# Orange_Board.net
KiCad netlist of a schematic drawn in EAGLE
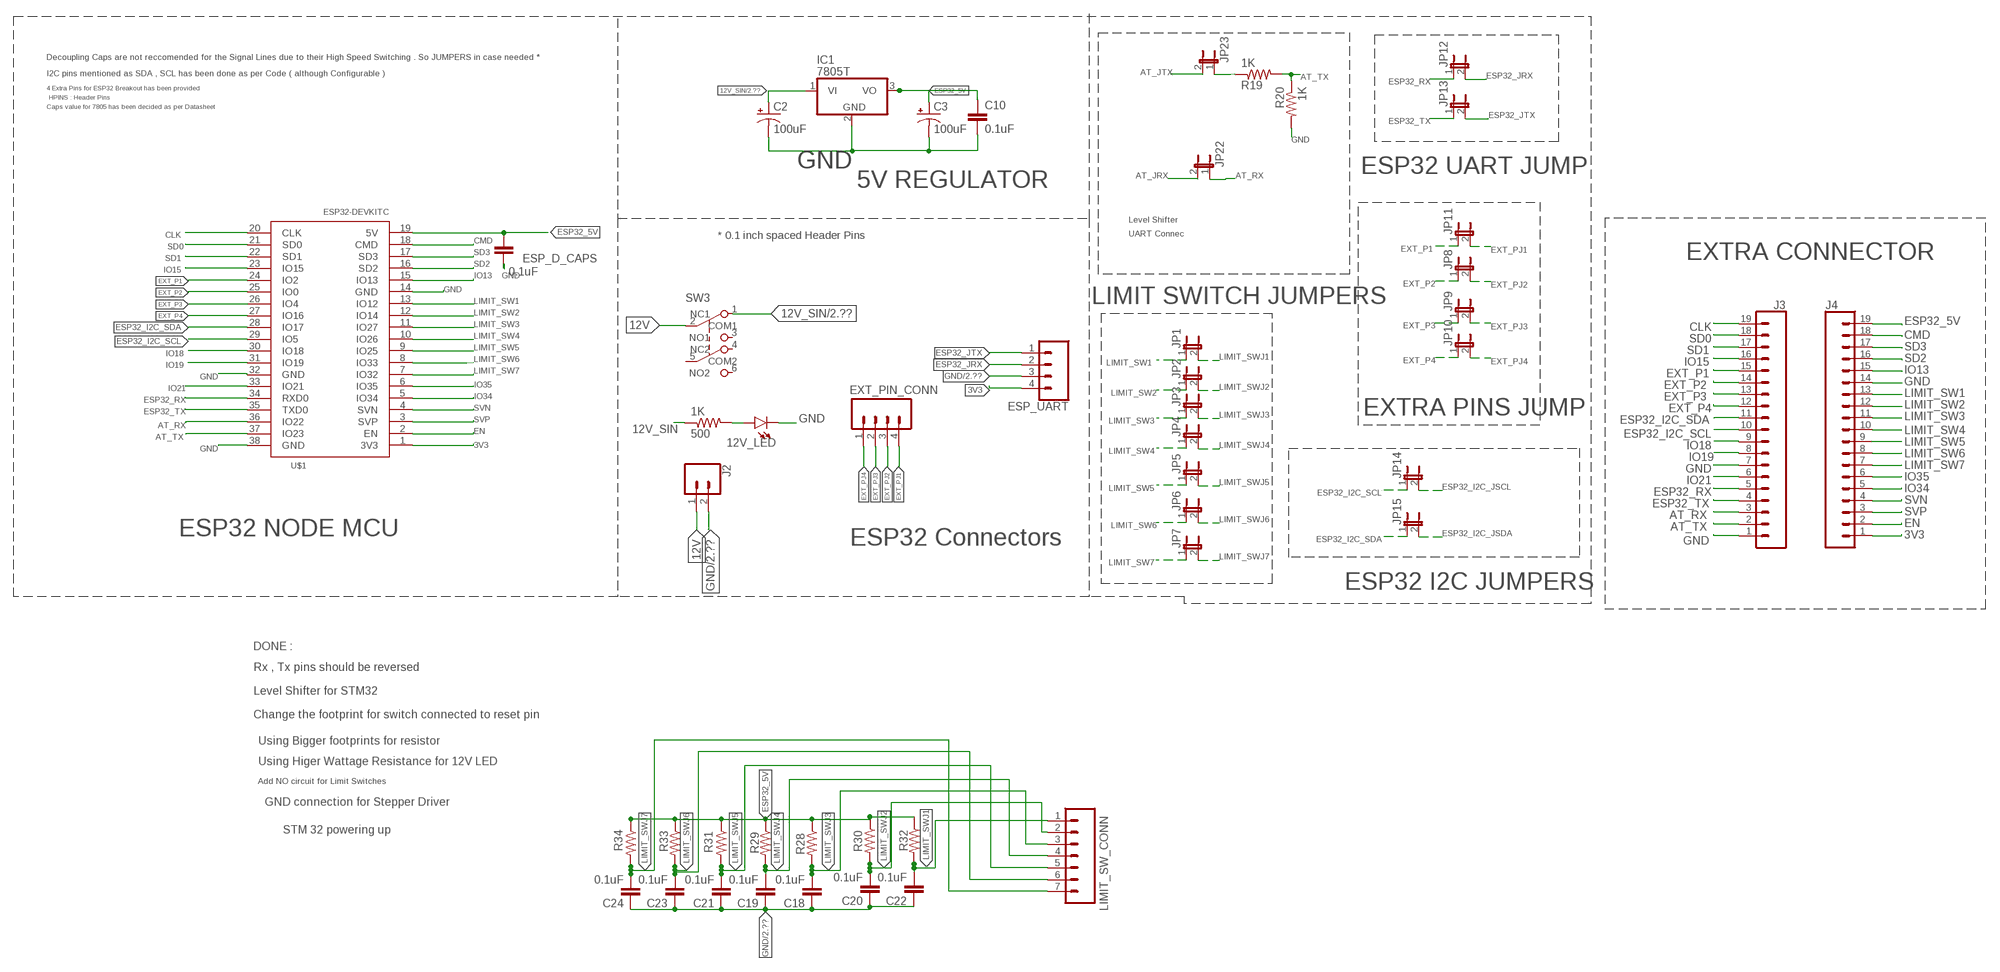
[diagram p0: schematic, sheet 1]
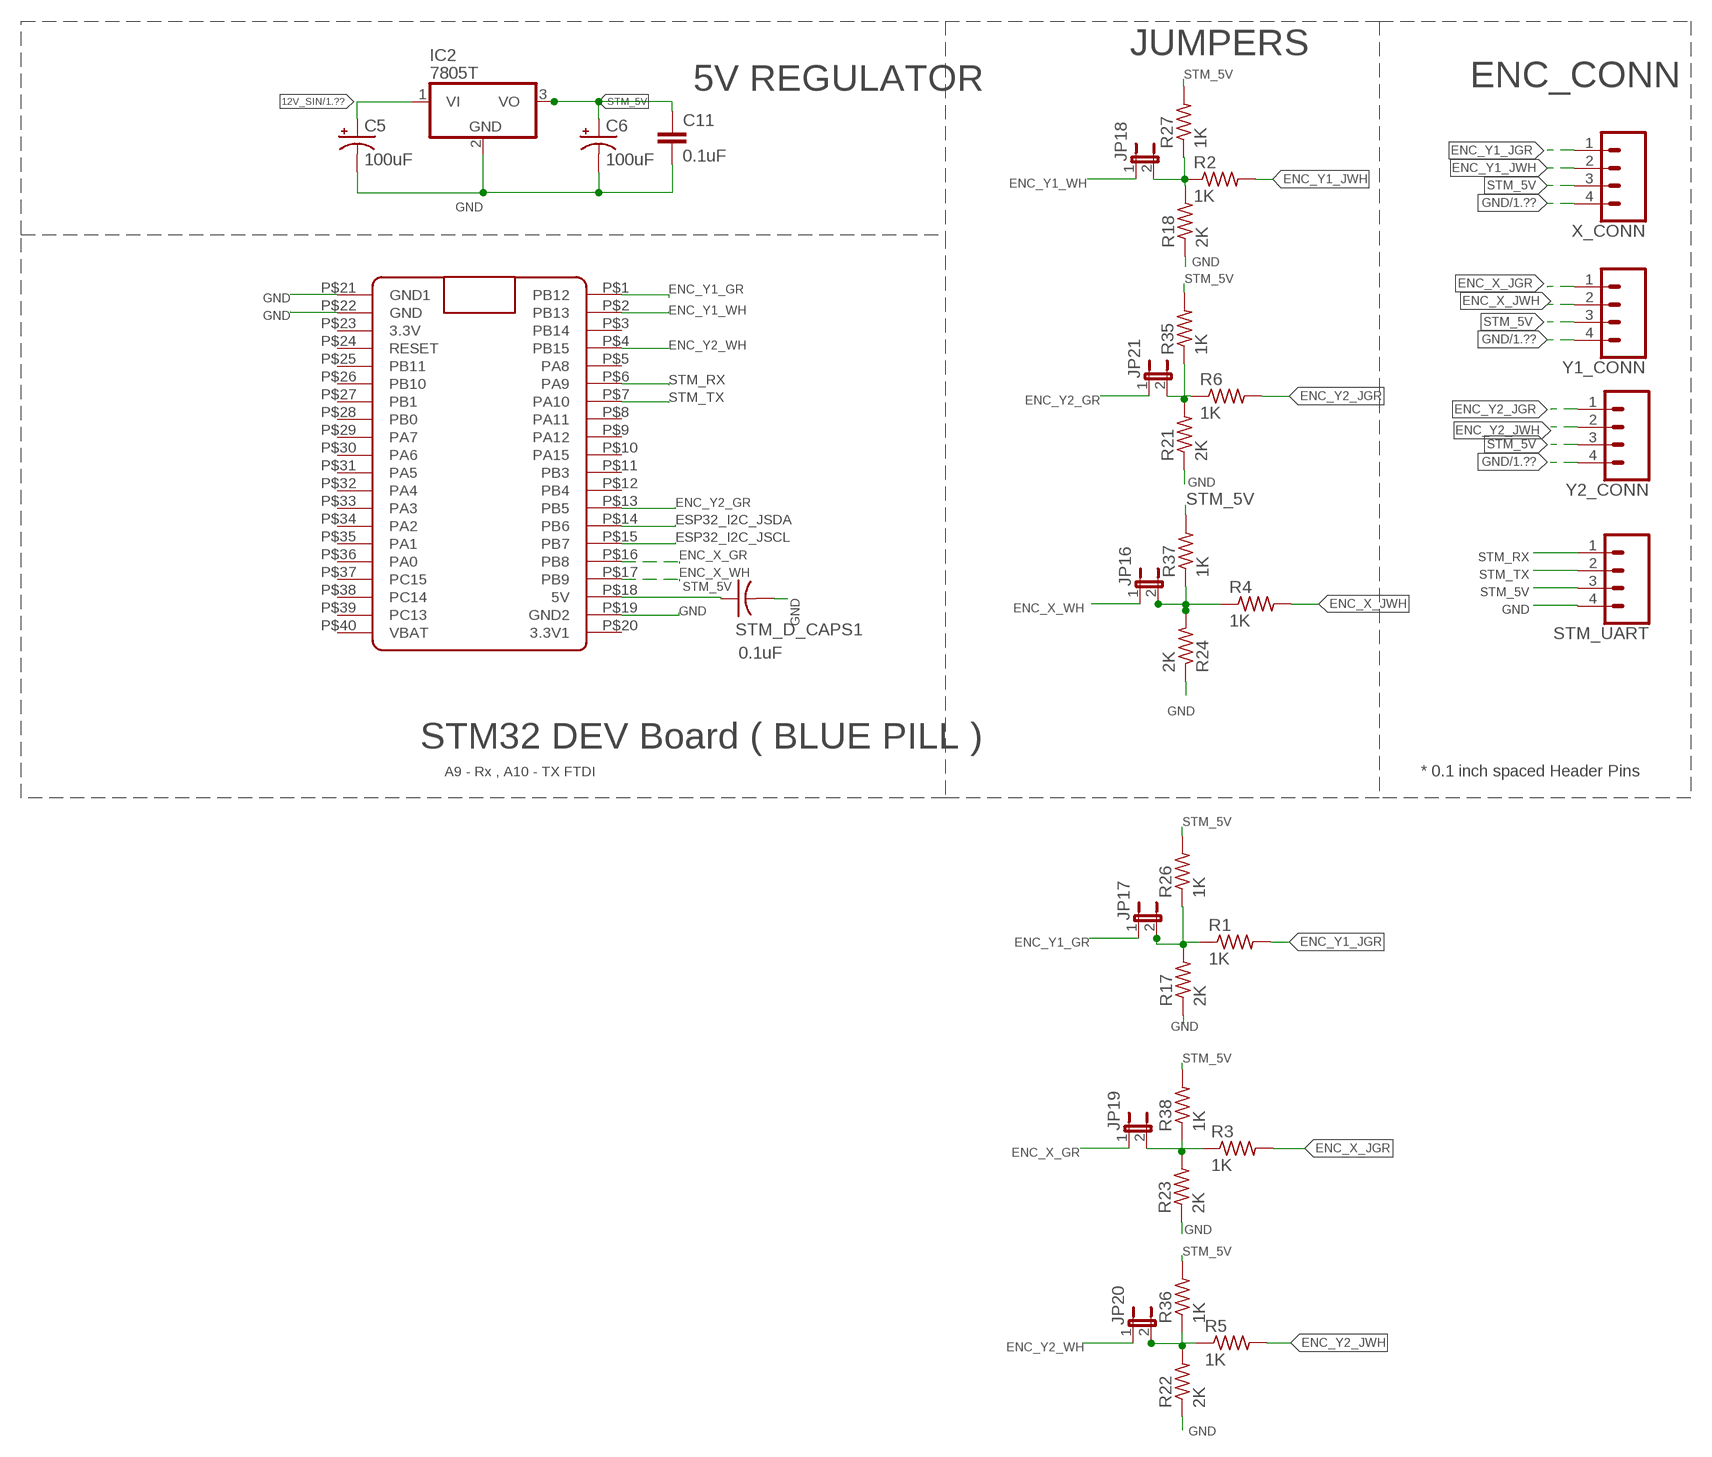
[diagram p1: schematic, sheet 2]
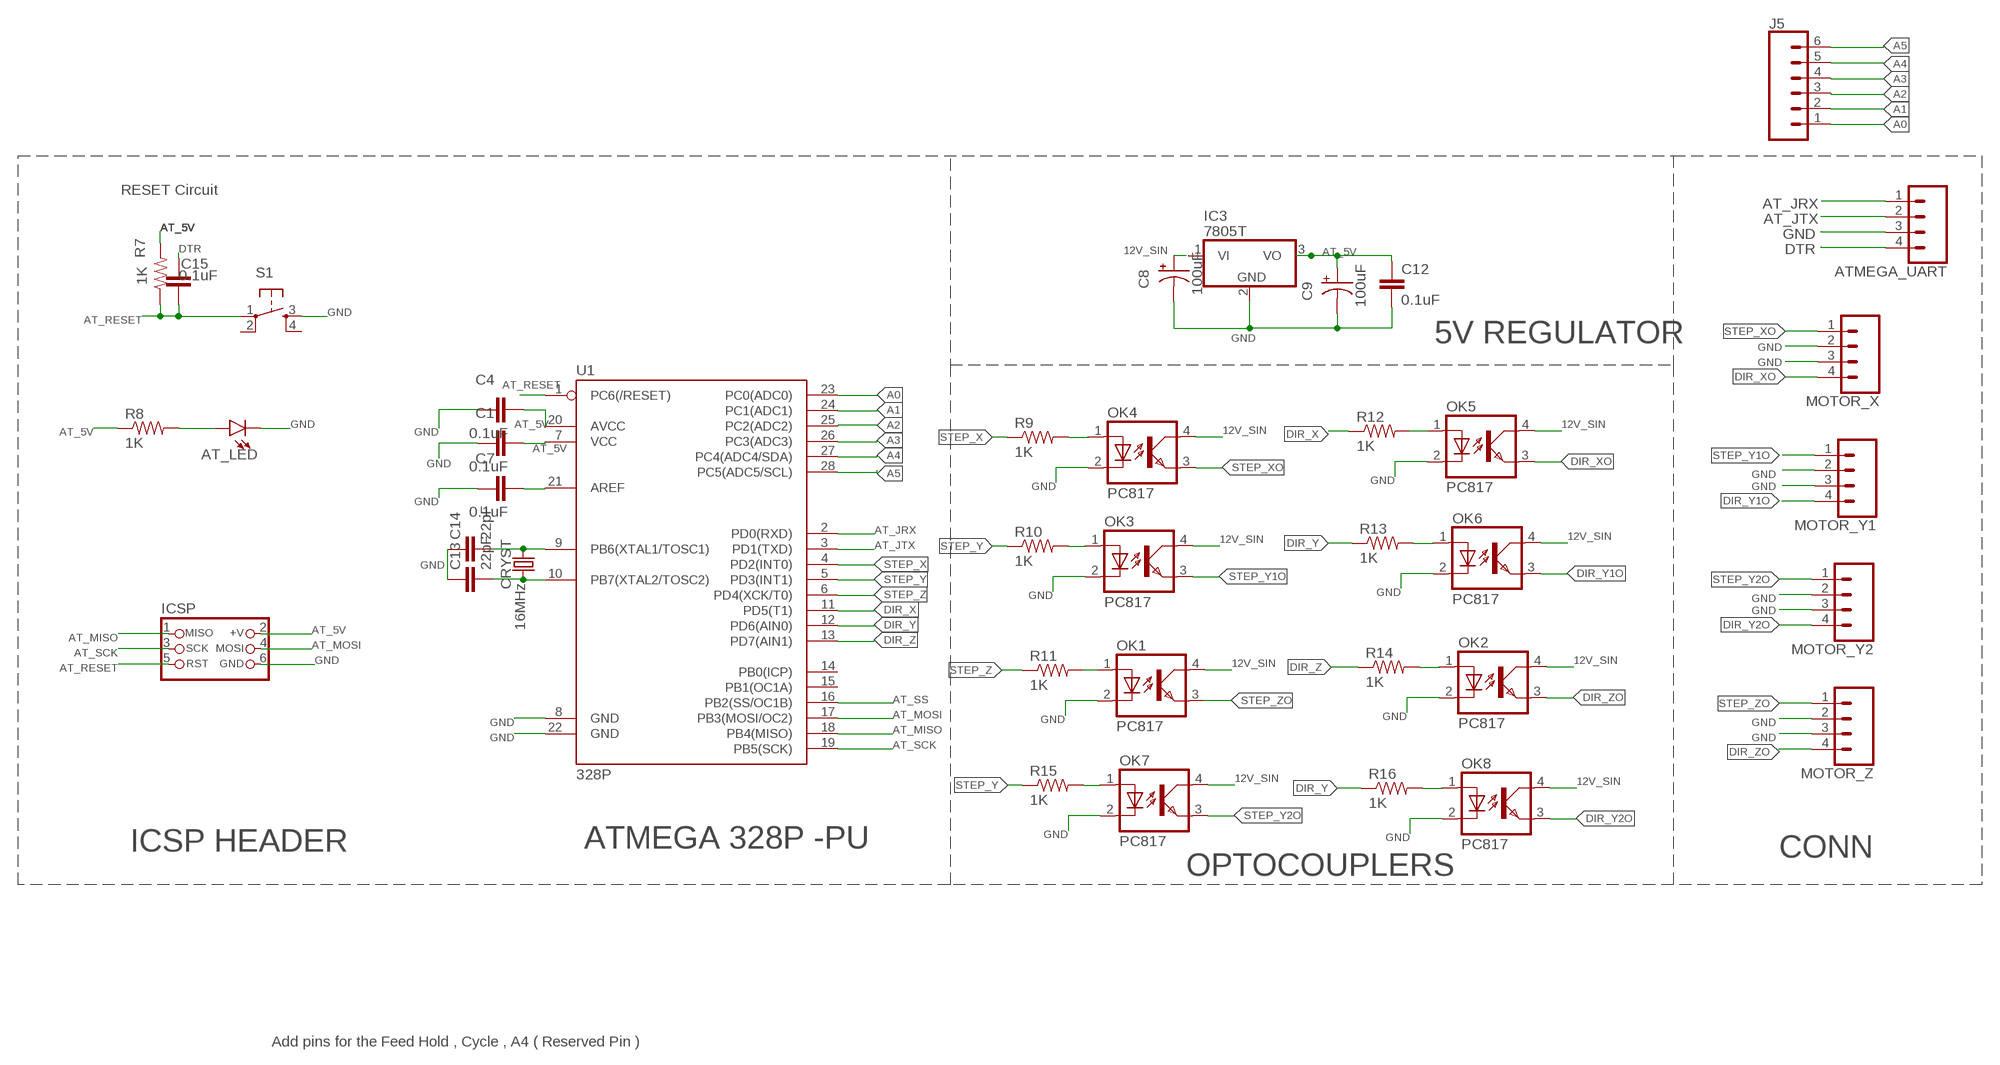
[diagram p2: schematic, sheet 3]

(export (version "E")
  (design (tool "Eeschema 10.0.6"))
  (components
    (comp (ref "C5")
      (value "100uF")
      (footprint "eagle-import:CPOL-RADIAL-2.5MM-6.5MM")
      (libsource (lib "eagle-import") (part "100UF-POLAR-RADIAL-2.5MM-25V-20%"))
    )
    (comp (ref "C6")
      (value "100uF")
      (footprint "eagle-import:CPOL-RADIAL-2.5MM-6.5MM")
      (libsource (lib "eagle-import") (part "100UF-POLAR-RADIAL-2.5MM-25V-20%"))
    )
    (comp (ref "C11")
      (value "0.1uF")
      (footprint "eagle-import:CAP-PTH-SMALL-KIT")
      (libsource (lib "eagle-import") (part "0.1UF-KIT-EZ-50V-20%"))
    )
    (comp (ref "IC2")
      (value "7805T")
      (footprint "eagle-import:TO220H")
      (libsource (lib "eagle-import") (part "78T05"))
    )
    (comp (ref "JP16")
      (value "JUMPER-2PTH")
      (footprint "eagle-import:1X02")
      (libsource (lib "eagle-import") (part "JUMPER-2PTH"))
    )
    (comp (ref "JP17")
      (value "JUMPER-2PTH")
      (footprint "eagle-import:1X02")
      (libsource (lib "eagle-import") (part "JUMPER-2PTH"))
    )
    (comp (ref "JP18")
      (value "JUMPER-2PTH")
      (footprint "eagle-import:1X02")
      (libsource (lib "eagle-import") (part "JUMPER-2PTH"))
    )
    (comp (ref "JP19")
      (value "JUMPER-2PTH")
      (footprint "eagle-import:1X02")
      (libsource (lib "eagle-import") (part "JUMPER-2PTH"))
    )
    (comp (ref "JP20")
      (value "JUMPER-2PTH")
      (footprint "eagle-import:1X02")
      (libsource (lib "eagle-import") (part "JUMPER-2PTH"))
    )
    (comp (ref "JP21")
      (value "JUMPER-2PTH")
      (footprint "eagle-import:1X02")
      (libsource (lib "eagle-import") (part "JUMPER-2PTH"))
    )
    (comp (ref "R1")
      (value "1K")
      (footprint "eagle-import:0207_10")
      (libsource (lib "eagle-import") (part "R-US_0207/10"))
    )
    (comp (ref "R2")
      (value "1K")
      (footprint "eagle-import:0207_10")
      (libsource (lib "eagle-import") (part "R-US_0207/10"))
    )
    (comp (ref "R3")
      (value "1K")
      (footprint "eagle-import:0207_10")
      (libsource (lib "eagle-import") (part "R-US_0207/10"))
    )
    (comp (ref "R4")
      (value "1K")
      (footprint "eagle-import:0207_10")
      (libsource (lib "eagle-import") (part "R-US_0207/10"))
    )
    (comp (ref "R5")
      (value "1K")
      (footprint "eagle-import:0207_10")
      (libsource (lib "eagle-import") (part "R-US_0207/10"))
    )
    (comp (ref "R6")
      (value "1K")
      (footprint "eagle-import:0207_10")
      (libsource (lib "eagle-import") (part "R-US_0207/10"))
    )
    (comp (ref "R17")
      (value "2K")
      (footprint "eagle-import:0207_10")
      (libsource (lib "eagle-import") (part "R-US_0207/10"))
    )
    (comp (ref "R18")
      (value "2K")
      (footprint "eagle-import:0207_10")
      (libsource (lib "eagle-import") (part "R-US_0207/10"))
    )
    (comp (ref "R21")
      (value "2K")
      (footprint "eagle-import:0207_10")
      (libsource (lib "eagle-import") (part "R-US_0207/10"))
    )
    (comp (ref "R22")
      (value "2K")
      (footprint "eagle-import:0207_10")
      (libsource (lib "eagle-import") (part "R-US_0207/10"))
    )
    (comp (ref "R23")
      (value "2K")
      (footprint "eagle-import:0207_10")
      (libsource (lib "eagle-import") (part "R-US_0207/10"))
    )
    (comp (ref "R24")
      (value "2K")
      (footprint "eagle-import:0207_10")
      (libsource (lib "eagle-import") (part "R-US_0207/10"))
    )
    (comp (ref "R26")
      (value "1K")
      (footprint "eagle-import:0207_10")
      (libsource (lib "eagle-import") (part "R-US_0207/10"))
    )
    (comp (ref "R27")
      (value "1K")
      (footprint "eagle-import:0207_10")
      (libsource (lib "eagle-import") (part "R-US_0207/10"))
    )
    (comp (ref "R35")
      (value "1K")
      (footprint "eagle-import:0207_10")
      (libsource (lib "eagle-import") (part "R-US_0207/10"))
    )
    (comp (ref "R36")
      (value "1K")
      (footprint "eagle-import:0207_10")
      (libsource (lib "eagle-import") (part "R-US_0207/10"))
    )
    (comp (ref "R37")
      (value "1K")
      (footprint "eagle-import:0207_10")
      (libsource (lib "eagle-import") (part "R-US_0207/10"))
    )
    (comp (ref "R38")
      (value "1K")
      (footprint "eagle-import:0207_10")
      (libsource (lib "eagle-import") (part "R-US_0207/10"))
    )
    (comp (ref "STM_D_CAPS1")
      (value "0.1uF")
      (footprint "eagle-import:C025-024X044")
      (libsource (lib "eagle-import") (part "C-US025-024X044"))
    )
    (comp (ref "STM_UART")
      (value "CONN_04")
      (footprint "eagle-import:1X04")
      (libsource (lib "eagle-import") (part "CONN_04"))
    )
    (comp (ref "U$2")
      (value "BLUE_PILLADVANCED")
      (footprint "eagle-import:BLUE_PILL_ADV")
      (libsource (lib "eagle-import") (part "BLUE_PILLADVANCED"))
    )
    (comp (ref "X_CONN")
      (value "CONN_04")
      (footprint "eagle-import:1X04")
      (libsource (lib "eagle-import") (part "CONN_04"))
    )
    (comp (ref "Y1_CONN")
      (value "CONN_04")
      (footprint "eagle-import:1X04")
      (libsource (lib "eagle-import") (part "CONN_04"))
    )
    (comp (ref "Y2_CONN")
      (value "CONN_04")
      (footprint "eagle-import:1X04")
      (libsource (lib "eagle-import") (part "CONN_04"))
    )
    (comp (ref "12V_LED")
      (value "LED-3MM-NO_SILK")
      (footprint "eagle-import:LED_3MM-NS")
      (libsource (lib "eagle-import") (part "LED-3MM-NO_SILK"))
    )
    (comp (ref "500")
      (value "1K")
      (footprint "eagle-import:0207_15")
      (libsource (lib "eagle-import") (part "R-US_0207/15"))
    )
    (comp (ref "C2")
      (value "100uF")
      (footprint "eagle-import:CPOL-RADIAL-2.5MM-6.5MM")
      (libsource (lib "eagle-import") (part "100UF-POLAR-RADIAL-2.5MM-25V-20%"))
    )
    (comp (ref "C3")
      (value "100uF")
      (footprint "eagle-import:CPOL-RADIAL-2.5MM-6.5MM")
      (libsource (lib "eagle-import") (part "100UF-POLAR-RADIAL-2.5MM-25V-20%"))
    )
    (comp (ref "C10")
      (value "0.1uF")
      (footprint "eagle-import:CAP-PTH-SMALL-KIT")
      (libsource (lib "eagle-import") (part "0.1UF-KIT-EZ-50V-20%"))
    )
    (comp (ref "C18")
      (value "0.1uF")
      (footprint "eagle-import:CAP-PTH-SMALL-KIT")
      (libsource (lib "eagle-import") (part "0.1UF-KIT-EZ-50V-20%"))
    )
    (comp (ref "C19")
      (value "0.1uF")
      (footprint "eagle-import:CAP-PTH-SMALL-KIT")
      (libsource (lib "eagle-import") (part "0.1UF-KIT-EZ-50V-20%"))
    )
    (comp (ref "C20")
      (value "0.1uF")
      (footprint "eagle-import:CAP-PTH-SMALL-KIT")
      (libsource (lib "eagle-import") (part "0.1UF-KIT-EZ-50V-20%"))
    )
    (comp (ref "C21")
      (value "0.1uF")
      (footprint "eagle-import:CAP-PTH-SMALL-KIT")
      (libsource (lib "eagle-import") (part "0.1UF-KIT-EZ-50V-20%"))
    )
    (comp (ref "C22")
      (value "0.1uF")
      (footprint "eagle-import:CAP-PTH-SMALL-KIT")
      (libsource (lib "eagle-import") (part "0.1UF-KIT-EZ-50V-20%"))
    )
    (comp (ref "C23")
      (value "0.1uF")
      (footprint "eagle-import:CAP-PTH-SMALL-KIT")
      (libsource (lib "eagle-import") (part "0.1UF-KIT-EZ-50V-20%"))
    )
    (comp (ref "C24")
      (value "0.1uF")
      (footprint "eagle-import:CAP-PTH-SMALL-KIT")
      (libsource (lib "eagle-import") (part "0.1UF-KIT-EZ-50V-20%"))
    )
    (comp (ref "ESP_D_CAPS")
      (value "0.1uF")
      (footprint "eagle-import:CAP-PTH-SMALL-KIT")
      (libsource (lib "eagle-import") (part "0.1UF-KIT-EZ-50V-20%"))
    )
    (comp (ref "ESP_UART")
      (value "CONN_04")
      (footprint "eagle-import:1X04")
      (libsource (lib "eagle-import") (part "CONN_04"))
    )
    (comp (ref "EXT_PIN_CONN")
      (value "CONN_04")
      (footprint "eagle-import:1X04")
      (libsource (lib "eagle-import") (part "CONN_04"))
    )
    (comp (ref "IC1")
      (value "7805T")
      (footprint "eagle-import:TO220H")
      (libsource (lib "eagle-import") (part "78T05"))
    )
    (comp (ref "J2")
      (value "CONN_025MM")
      (footprint "eagle-import:SCREWTERMINAL-5MM-2")
      (libsource (lib "eagle-import") (part "CONN_025MM"))
    )
    (comp (ref "J3")
      (value "CONN_19")
      (footprint "eagle-import:1X19")
      (libsource (lib "eagle-import") (part "CONN_19"))
    )
    (comp (ref "J4")
      (value "CONN_19")
      (footprint "eagle-import:1X19")
      (libsource (lib "eagle-import") (part "CONN_19"))
    )
    (comp (ref "JP1")
      (value "JUMPER-2PTH")
      (footprint "eagle-import:1X02")
      (libsource (lib "eagle-import") (part "JUMPER-2PTH"))
    )
    (comp (ref "JP2")
      (value "JUMPER-2PTH")
      (footprint "eagle-import:1X02")
      (libsource (lib "eagle-import") (part "JUMPER-2PTH"))
    )
    (comp (ref "JP3")
      (value "JUMPER-2PTH")
      (footprint "eagle-import:1X02")
      (libsource (lib "eagle-import") (part "JUMPER-2PTH"))
    )
    (comp (ref "JP4")
      (value "JUMPER-2PTH")
      (footprint "eagle-import:1X02")
      (libsource (lib "eagle-import") (part "JUMPER-2PTH"))
    )
    (comp (ref "JP5")
      (value "JUMPER-2PTH")
      (footprint "eagle-import:1X02")
      (libsource (lib "eagle-import") (part "JUMPER-2PTH"))
    )
    (comp (ref "JP6")
      (value "JUMPER-2PTH")
      (footprint "eagle-import:1X02")
      (libsource (lib "eagle-import") (part "JUMPER-2PTH"))
    )
    (comp (ref "JP7")
      (value "JUMPER-2PTH")
      (footprint "eagle-import:1X02")
      (libsource (lib "eagle-import") (part "JUMPER-2PTH"))
    )
    (comp (ref "JP8")
      (value "JUMPER-2PTH")
      (footprint "eagle-import:1X02")
      (libsource (lib "eagle-import") (part "JUMPER-2PTH"))
    )
    (comp (ref "JP9")
      (value "JUMPER-2PTH")
      (footprint "eagle-import:1X02")
      (libsource (lib "eagle-import") (part "JUMPER-2PTH"))
    )
    (comp (ref "JP10")
      (value "JUMPER-2PTH")
      (footprint "eagle-import:1X02")
      (libsource (lib "eagle-import") (part "JUMPER-2PTH"))
    )
    (comp (ref "JP11")
      (value "JUMPER-2PTH")
      (footprint "eagle-import:1X02")
      (libsource (lib "eagle-import") (part "JUMPER-2PTH"))
    )
    (comp (ref "JP12")
      (value "JUMPER-2PTH")
      (footprint "eagle-import:1X02")
      (libsource (lib "eagle-import") (part "JUMPER-2PTH"))
    )
    (comp (ref "JP13")
      (value "JUMPER-2PTH")
      (footprint "eagle-import:1X02")
      (libsource (lib "eagle-import") (part "JUMPER-2PTH"))
    )
    (comp (ref "JP14")
      (value "JUMPER-2PTH")
      (footprint "eagle-import:1X02")
      (libsource (lib "eagle-import") (part "JUMPER-2PTH"))
    )
    (comp (ref "JP15")
      (value "JUMPER-2PTH")
      (footprint "eagle-import:1X02")
      (libsource (lib "eagle-import") (part "JUMPER-2PTH"))
    )
    (comp (ref "JP22")
      (value "JUMPER-2PTH")
      (footprint "eagle-import:1X02")
      (libsource (lib "eagle-import") (part "JUMPER-2PTH"))
    )
    (comp (ref "JP23")
      (value "JUMPER-2PTH")
      (footprint "eagle-import:1X02")
      (libsource (lib "eagle-import") (part "JUMPER-2PTH"))
    )
    (comp (ref "LIMIT_SW_CONN")
      (value "CONN_07")
      (footprint "eagle-import:1X07")
      (libsource (lib "eagle-import") (part "CONN_07"))
    )
    (comp (ref "R19")
      (value "1K")
      (footprint "eagle-import:0207_10")
      (libsource (lib "eagle-import") (part "R-US_0207/10"))
    )
    (comp (ref "R20")
      (value "1K")
      (footprint "eagle-import:0207_10")
      (libsource (lib "eagle-import") (part "R-US_0207/10"))
    )
    (comp (ref "R28")
      (value "R-US_0207/10")
      (footprint "eagle-import:0207_10")
      (libsource (lib "eagle-import") (part "R-US_0207/10"))
    )
    (comp (ref "R29")
      (value "R-US_0207/10")
      (footprint "eagle-import:0207_10")
      (libsource (lib "eagle-import") (part "R-US_0207/10"))
    )
    (comp (ref "R30")
      (value "R-US_0207/10")
      (footprint "eagle-import:0207_10")
      (libsource (lib "eagle-import") (part "R-US_0207/10"))
    )
    (comp (ref "R31")
      (value "R-US_0207/10")
      (footprint "eagle-import:0207_10")
      (libsource (lib "eagle-import") (part "R-US_0207/10"))
    )
    (comp (ref "R32")
      (value "R-US_0207/10")
      (footprint "eagle-import:0207_10")
      (libsource (lib "eagle-import") (part "R-US_0207/10"))
    )
    (comp (ref "R33")
      (value "R-US_0207/10")
      (footprint "eagle-import:0207_10")
      (libsource (lib "eagle-import") (part "R-US_0207/10"))
    )
    (comp (ref "R34")
      (value "R-US_0207/10")
      (footprint "eagle-import:0207_10")
      (libsource (lib "eagle-import") (part "R-US_0207/10"))
    )
    (comp (ref "SW3")
      (value "SW_PUSH_DPDT")
      (footprint "eagle-import:SW_PUSH_BUTTON_MINI")
      (libsource (lib "eagle-import") (part "SW_PUSH_DPDT"))
    )
    (comp (ref "U$1")
      (value "ESP32DEVKITC")
      (footprint "eagle-import:ESP32-DEVKITC")
      (libsource (lib "eagle-import") (part "ESP32DEVKITC"))
    )
    (comp (ref "ATMEGA_UART")
      (value "CONN_04")
      (footprint "eagle-import:1X04")
      (libsource (lib "eagle-import") (part "CONN_04"))
    )
    (comp (ref "AT_LED")
      (value "LED-3MM-NO_SILK")
      (footprint "eagle-import:LED_3MM-NS")
      (libsource (lib "eagle-import") (part "LED-3MM-NO_SILK"))
    )
    (comp (ref "C1")
      (value "0.1uF")
      (footprint "eagle-import:CAP-PTH-SMALL-KIT")
      (libsource (lib "eagle-import") (part "0.1UF-KIT-EZ-50V-20%"))
    )
    (comp (ref "C4")
      (value "0.1uF")
      (footprint "eagle-import:CAP-PTH-SMALL-KIT")
      (libsource (lib "eagle-import") (part "0.1UF-KIT-EZ-50V-20%"))
    )
    (comp (ref "C7")
      (value "0.1uF")
      (footprint "eagle-import:CAP-PTH-SMALL-KIT")
      (libsource (lib "eagle-import") (part "0.1UF-KIT-EZ-50V-20%"))
    )
    (comp (ref "C8")
      (value "100uF")
      (footprint "eagle-import:CPOL-RADIAL-2.5MM-6.5MM")
      (libsource (lib "eagle-import") (part "100UF-POLAR-RADIAL-2.5MM-25V-20%"))
    )
    (comp (ref "C9")
      (value "100uF")
      (footprint "eagle-import:CPOL-RADIAL-2.5MM-6.5MM")
      (libsource (lib "eagle-import") (part "100UF-POLAR-RADIAL-2.5MM-25V-20%"))
    )
    (comp (ref "C12")
      (value "0.1uF")
      (footprint "eagle-import:CAP-PTH-SMALL-KIT")
      (libsource (lib "eagle-import") (part "0.1UF-KIT-EZ-50V-20%"))
    )
    (comp (ref "C13")
      (value "22pF")
      (footprint "eagle-import:CAP-PTH-2.54")
      (libsource (lib "eagle-import") (part "22PF-PTH-2.54MM-200V-5%"))
    )
    (comp (ref "C14")
      (value "22pF")
      (footprint "eagle-import:CAP-PTH-2.54")
      (libsource (lib "eagle-import") (part "22PF-PTH-2.54MM-200V-5%"))
    )
    (comp (ref "C15")
      (value "0.1uF")
      (footprint "eagle-import:CAP-PTH-SMALL-KIT")
      (libsource (lib "eagle-import") (part "0.1UF-KIT-EZ-50V-20%"))
    )
    (comp (ref "CRYST")
      (value "16MHz")
      (footprint "eagle-import:HC49US")
      (libsource (lib "eagle-import") (part "CRYSTAL-16MHZPTH-HC49US"))
    )
    (comp (ref "IC3")
      (value "7805T")
      (footprint "eagle-import:TO220H")
      (libsource (lib "eagle-import") (part "78T05"))
    )
    (comp (ref "ICSP")
      (value "CON_HEADER_PRG_AVR_ICSP-PTH")
      (footprint "eagle-import:HEADER_PRG_2X03")
      (libsource (lib "eagle-import") (part "CON_HEADER_PRG_AVR_ICSP-PTH"))
    )
    (comp (ref "J5")
      (value "CONN_06NO_SILK_FEMALE_PTH")
      (footprint "eagle-import:1X06_NO_SILK")
      (libsource (lib "eagle-import") (part "CONN_06NO_SILK_FEMALE_PTH"))
    )
    (comp (ref "MOTOR_X")
      (value "CONN_04")
      (footprint "eagle-import:1X04")
      (libsource (lib "eagle-import") (part "CONN_04"))
    )
    (comp (ref "MOTOR_Y1")
      (value "CONN_04")
      (footprint "eagle-import:1X04")
      (libsource (lib "eagle-import") (part "CONN_04"))
    )
    (comp (ref "MOTOR_Y2")
      (value "CONN_04")
      (footprint "eagle-import:1X04")
      (libsource (lib "eagle-import") (part "CONN_04"))
    )
    (comp (ref "MOTOR_Z")
      (value "CONN_04")
      (footprint "eagle-import:1X04")
      (libsource (lib "eagle-import") (part "CONN_04"))
    )
    (comp (ref "OK1")
      (value "PC817")
      (footprint "eagle-import:DIL04")
      (fields (field (name "MPN") "PC817X4J000F"))
      (libsource (lib "eagle-import") (part "PC817"))
    )
    (comp (ref "OK2")
      (value "PC817")
      (footprint "eagle-import:DIL04")
      (fields (field (name "MPN") "PC817X4J000F"))
      (libsource (lib "eagle-import") (part "PC817"))
    )
    (comp (ref "OK3")
      (value "PC817")
      (footprint "eagle-import:DIL04")
      (fields (field (name "MPN") "PC817X4J000F"))
      (libsource (lib "eagle-import") (part "PC817"))
    )
    (comp (ref "OK4")
      (value "PC817")
      (footprint "eagle-import:DIL04")
      (fields (field (name "MPN") "PC817X4J000F"))
      (libsource (lib "eagle-import") (part "PC817"))
    )
    (comp (ref "OK5")
      (value "PC817")
      (footprint "eagle-import:DIL04")
      (fields (field (name "MPN") "PC817X4J000F"))
      (libsource (lib "eagle-import") (part "PC817"))
    )
    (comp (ref "OK6")
      (value "PC817")
      (footprint "eagle-import:DIL04")
      (fields (field (name "MPN") "PC817X4J000F"))
      (libsource (lib "eagle-import") (part "PC817"))
    )
    (comp (ref "OK7")
      (value "PC817")
      (footprint "eagle-import:DIL04")
      (fields (field (name "MPN") "PC817X4J000F"))
      (libsource (lib "eagle-import") (part "PC817"))
    )
    (comp (ref "OK8")
      (value "PC817")
      (footprint "eagle-import:DIL04")
      (fields (field (name "MPN") "PC817X4J000F"))
      (libsource (lib "eagle-import") (part "PC817"))
    )
    (comp (ref "R7")
      (value "1K")
      (footprint "eagle-import:0207_10")
      (libsource (lib "eagle-import") (part "R-US_0207/10"))
    )
    (comp (ref "R8")
      (value "1K")
      (footprint "eagle-import:0207_10")
      (libsource (lib "eagle-import") (part "R-US_0207/10"))
    )
    (comp (ref "R9")
      (value "1K")
      (footprint "eagle-import:0207_10")
      (libsource (lib "eagle-import") (part "R-US_0207/10"))
    )
    (comp (ref "R10")
      (value "1K")
      (footprint "eagle-import:0207_10")
      (libsource (lib "eagle-import") (part "R-US_0207/10"))
    )
    (comp (ref "R11")
      (value "1K")
      (footprint "eagle-import:0207_10")
      (libsource (lib "eagle-import") (part "R-US_0207/10"))
    )
    (comp (ref "R12")
      (value "1K")
      (footprint "eagle-import:0207_10")
      (libsource (lib "eagle-import") (part "R-US_0207/10"))
    )
    (comp (ref "R13")
      (value "1K")
      (footprint "eagle-import:0207_10")
      (libsource (lib "eagle-import") (part "R-US_0207/10"))
    )
    (comp (ref "R14")
      (value "1K")
      (footprint "eagle-import:0207_10")
      (libsource (lib "eagle-import") (part "R-US_0207/10"))
    )
    (comp (ref "R15")
      (value "1K")
      (footprint "eagle-import:0207_10")
      (libsource (lib "eagle-import") (part "R-US_0207/10"))
    )
    (comp (ref "R16")
      (value "1K")
      (footprint "eagle-import:0207_10")
      (libsource (lib "eagle-import") (part "R-US_0207/10"))
    )
    (comp (ref "S1")
      (value "TAC_SWITCHPTH")
      (footprint "eagle-import:TACTILE-PTH")
      (libsource (lib "eagle-import") (part "TAC_SWITCHPTH"))
    )
    (comp (ref "U1")
      (value "328P")
      (footprint "eagle-import:DIP28")
      (libsource (lib "eagle-import") (part "ATMEGA328P_PDIP"))
    )
  )
  (nets
    (net (code "1") (name "3V3") (class "Default")
      (node (ref "ESP_UART") (pin "4") (pinfunction "4_4") (pintype "passive"))
      (node (ref "J4") (pin "1") (pinfunction "1_1") (pintype "passive"))
      (node (ref "U$1") (pin "1") (pinfunction "3V3_1") (pintype "bidirectional"))
    )
    (net (code "2") (name "12V") (class "Default")
      (node (ref "J2") (pin "1") (pinfunction "1_1") (pintype "passive"))
      (node (ref "SW3") (pin "2") (pinfunction "COM1_2") (pintype "passive"))
    )
    (net (code "3") (name "12V_SIN") (class "Default")
      (node (ref "500") (pin "1") (pinfunction "1_1") (pintype "passive"))
      (node (ref "C2") (pin "1") (pinfunction "+_1") (pintype "passive"))
      (node (ref "C5") (pin "1") (pinfunction "+_1") (pintype "passive"))
      (node (ref "C8") (pin "1") (pinfunction "+_1") (pintype "passive"))
      (node (ref "IC1") (pin "1") (pinfunction "VI_1") (pintype "input"))
      (node (ref "IC2") (pin "1") (pinfunction "VI_1") (pintype "input"))
      (node (ref "IC3") (pin "1") (pinfunction "VI_1") (pintype "input"))
      (node (ref "OK1") (pin "4") (pinfunction "COL_4") (pintype "passive"))
      (node (ref "OK2") (pin "4") (pinfunction "COL_4") (pintype "passive"))
      (node (ref "OK3") (pin "4") (pinfunction "COL_4") (pintype "passive"))
      (node (ref "OK4") (pin "4") (pinfunction "COL_4") (pintype "passive"))
      (node (ref "OK5") (pin "4") (pinfunction "COL_4") (pintype "passive"))
      (node (ref "OK6") (pin "4") (pinfunction "COL_4") (pintype "passive"))
      (node (ref "OK7") (pin "4") (pinfunction "COL_4") (pintype "passive"))
      (node (ref "OK8") (pin "4") (pinfunction "COL_4") (pintype "passive"))
      (node (ref "SW3") (pin "1") (pinfunction "NC1_1") (pintype "passive"))
    )
    (net (code "4") (name "A0") (class "Default")
      (node (ref "J5") (pin "1") (pinfunction "1_1") (pintype "passive"))
      (node (ref "U1") (pin "23") (pinfunction "PC0(ADC0)_23") (pintype "bidirectional"))
    )
    (net (code "5") (name "A1") (class "Default")
      (node (ref "J5") (pin "2") (pinfunction "2_2") (pintype "passive"))
      (node (ref "U1") (pin "24") (pinfunction "PC1(ADC1)_24") (pintype "bidirectional"))
    )
    (net (code "6") (name "A2") (class "Default")
      (node (ref "J5") (pin "3") (pinfunction "3_3") (pintype "passive"))
      (node (ref "U1") (pin "25") (pinfunction "PC2(ADC2)_25") (pintype "bidirectional"))
    )
    (net (code "7") (name "A3") (class "Default")
      (node (ref "J5") (pin "4") (pinfunction "4_4") (pintype "passive"))
      (node (ref "U1") (pin "26") (pinfunction "PC3(ADC3)_26") (pintype "bidirectional"))
    )
    (net (code "8") (name "A4") (class "Default")
      (node (ref "J5") (pin "5") (pinfunction "5_5") (pintype "passive"))
      (node (ref "U1") (pin "27") (pinfunction "PC4(ADC4/SDA)_27") (pintype "bidirectional"))
    )
    (net (code "9") (name "A5") (class "Default")
      (node (ref "J5") (pin "6") (pinfunction "6_6") (pintype "passive"))
      (node (ref "U1") (pin "28") (pinfunction "PC5(ADC5/SCL)_28") (pintype "bidirectional"))
    )
    (net (code "10") (name "AT_5V") (class "Default")
      (node (ref "C1") (pin "1") (pinfunction "1_1") (pintype "passive"))
      (node (ref "C12") (pin "1") (pinfunction "1_1") (pintype "passive"))
      (node (ref "C4") (pin "1") (pinfunction "1_1") (pintype "passive"))
      (node (ref "C9") (pin "1") (pinfunction "+_1") (pintype "passive"))
      (node (ref "IC3") (pin "3") (pinfunction "VO_3") (pintype "passive"))
      (node (ref "ICSP") (pin "2") (pinfunction "+V_2") (pintype "passive"))
      (node (ref "R7") (pin "2") (pinfunction "2_2") (pintype "passive"))
      (node (ref "R8") (pin "1") (pinfunction "1_1") (pintype "passive"))
      (node (ref "U1") (pin "20") (pinfunction "AVCC_20") (pintype "bidirectional"))
      (node (ref "U1") (pin "7") (pinfunction "VCC_7") (pintype "bidirectional"))
    )
    (net (code "11") (name "AT_JRX") (class "Default")
      (node (ref "ATMEGA_UART") (pin "1") (pinfunction "1_1") (pintype "passive"))
      (node (ref "JP22") (pin "2") (pinfunction "2_2") (pintype "passive"))
      (node (ref "U1") (pin "2") (pinfunction "PD0(RXD)_2") (pintype "bidirectional"))
    )
    (net (code "12") (name "AT_JTX") (class "Default")
      (node (ref "ATMEGA_UART") (pin "2") (pinfunction "2_2") (pintype "passive"))
      (node (ref "JP23") (pin "2") (pinfunction "2_2") (pintype "passive"))
      (node (ref "U1") (pin "3") (pinfunction "PD1(TXD)_3") (pintype "bidirectional"))
    )
    (net (code "13") (name "AT_MISO") (class "Default")
      (node (ref "ICSP") (pin "1") (pinfunction "MISO_1") (pintype "passive"))
      (node (ref "U1") (pin "18") (pinfunction "PB4(MISO)_18") (pintype "bidirectional"))
    )
    (net (code "14") (name "AT_MOSI") (class "Default")
      (node (ref "ICSP") (pin "4") (pinfunction "MOSI_4") (pintype "passive"))
      (node (ref "U1") (pin "17") (pinfunction "PB3(MOSI/OC2)_17") (pintype "bidirectional"))
    )
    (net (code "15") (name "AT_RESET") (class "Default")
      (node (ref "C15") (pin "1") (pinfunction "1_1") (pintype "passive"))
      (node (ref "ICSP") (pin "5") (pinfunction "RST_5") (pintype "passive"))
      (node (ref "R7") (pin "1") (pinfunction "1_1") (pintype "passive"))
      (node (ref "S1") (pin "1") (pinfunction "1_1") (pintype "passive"))
      (node (ref "U1") (pin "1") (pinfunction "PC6(/RESET)_1") (pintype "bidirectional"))
    )
    (net (code "16") (name "AT_RX") (class "Default")
      (node (ref "J3") (pin "3") (pinfunction "3_3") (pintype "passive"))
      (node (ref "JP22") (pin "1") (pinfunction "1_1") (pintype "passive"))
      (node (ref "U$1") (pin "36") (pinfunction "IO22_36") (pintype "bidirectional"))
    )
    (net (code "17") (name "AT_SCK") (class "Default")
      (node (ref "ICSP") (pin "3") (pinfunction "SCK_3") (pintype "passive"))
      (node (ref "U1") (pin "19") (pinfunction "PB5(SCK)_19") (pintype "bidirectional"))
    )
    (net (code "18") (name "AT_SS") (class "Default")
      (node (ref "U1") (pin "16") (pinfunction "PB2(SS/OC1B)_16") (pintype "bidirectional"))
    )
    (net (code "19") (name "AT_TX") (class "Default")
      (node (ref "J3") (pin "2") (pinfunction "2_2") (pintype "passive"))
      (node (ref "R19") (pin "2") (pinfunction "2_2") (pintype "passive"))
      (node (ref "R20") (pin "1") (pinfunction "1_1") (pintype "passive"))
      (node (ref "U$1") (pin "37") (pinfunction "IO23_37") (pintype "bidirectional"))
    )
    (net (code "20") (name "CLK") (class "Default")
      (node (ref "J3") (pin "19") (pinfunction "19_19") (pintype "passive"))
      (node (ref "U$1") (pin "20") (pinfunction "CLK_20") (pintype "bidirectional"))
    )
    (net (code "21") (name "CMD") (class "Default")
      (node (ref "J4") (pin "18") (pinfunction "18_18") (pintype "passive"))
      (node (ref "U$1") (pin "18") (pinfunction "CMD_18") (pintype "bidirectional"))
    )
    (net (code "22") (name "DIR_X") (class "Default")
      (node (ref "R12") (pin "1") (pinfunction "1_1") (pintype "passive"))
      (node (ref "U1") (pin "11") (pinfunction "PD5(T1)_11") (pintype "bidirectional"))
    )
    (net (code "23") (name "DIR_XO") (class "Default")
      (node (ref "MOTOR_X") (pin "4") (pinfunction "4_4") (pintype "passive"))
      (node (ref "OK5") (pin "3") (pinfunction "EMIT_3") (pintype "passive"))
    )
    (net (code "24") (name "DIR_Y") (class "Default")
      (node (ref "R13") (pin "1") (pinfunction "1_1") (pintype "passive"))
      (node (ref "R16") (pin "1") (pinfunction "1_1") (pintype "passive"))
      (node (ref "U1") (pin "12") (pinfunction "PD6(AIN0)_12") (pintype "bidirectional"))
    )
    (net (code "25") (name "DIR_Y1O") (class "Default")
      (node (ref "MOTOR_Y1") (pin "4") (pinfunction "4_4") (pintype "passive"))
      (node (ref "OK6") (pin "3") (pinfunction "EMIT_3") (pintype "passive"))
    )
    (net (code "26") (name "DIR_Y2O") (class "Default")
      (node (ref "MOTOR_Y2") (pin "4") (pinfunction "4_4") (pintype "passive"))
      (node (ref "OK8") (pin "3") (pinfunction "EMIT_3") (pintype "passive"))
    )
    (net (code "27") (name "DIR_Z") (class "Default")
      (node (ref "R14") (pin "1") (pinfunction "1_1") (pintype "passive"))
      (node (ref "U1") (pin "13") (pinfunction "PD7(AIN1)_13") (pintype "bidirectional"))
    )
    (net (code "28") (name "DIR_ZO") (class "Default")
      (node (ref "MOTOR_Z") (pin "4") (pinfunction "4_4") (pintype "passive"))
      (node (ref "OK2") (pin "3") (pinfunction "EMIT_3") (pintype "passive"))
    )
    (net (code "29") (name "DTR") (class "Default")
      (node (ref "ATMEGA_UART") (pin "4") (pinfunction "4_4") (pintype "passive"))
      (node (ref "C15") (pin "2") (pinfunction "2_2") (pintype "passive"))
    )
    (net (code "30") (name "EN") (class "Default")
      (node (ref "J4") (pin "2") (pinfunction "2_2") (pintype "passive"))
      (node (ref "U$1") (pin "2") (pinfunction "EN_2") (pintype "bidirectional"))
    )
    (net (code "31") (name "ENC_X_GR") (class "Default")
      (node (ref "JP19") (pin "1") (pinfunction "1_1") (pintype "passive"))
      (node (ref "U$2") (pin "P$16") (pinfunction "PB8_P$16") (pintype "bidirectional"))
    )
    (net (code "32") (name "ENC_X_JGR") (class "Default")
      (node (ref "R3") (pin "2") (pinfunction "2_2") (pintype "passive"))
      (node (ref "Y1_CONN") (pin "1") (pinfunction "1_1") (pintype "passive"))
    )
    (net (code "33") (name "ENC_X_JWH") (class "Default")
      (node (ref "R4") (pin "2") (pinfunction "2_2") (pintype "passive"))
      (node (ref "Y1_CONN") (pin "2") (pinfunction "2_2") (pintype "passive"))
    )
    (net (code "34") (name "ENC_X_WH") (class "Default")
      (node (ref "JP16") (pin "1") (pinfunction "1_1") (pintype "passive"))
      (node (ref "U$2") (pin "P$17") (pinfunction "PB9_P$17") (pintype "bidirectional"))
    )
    (net (code "35") (name "ENC_Y1_GR") (class "Default")
      (node (ref "JP17") (pin "1") (pinfunction "1_1") (pintype "passive"))
      (node (ref "U$2") (pin "P$1") (pinfunction "PB12_P$1") (pintype "bidirectional"))
    )
    (net (code "36") (name "ENC_Y1_JGR") (class "Default")
      (node (ref "R1") (pin "2") (pinfunction "2_2") (pintype "passive"))
      (node (ref "X_CONN") (pin "1") (pinfunction "1_1") (pintype "passive"))
    )
    (net (code "37") (name "ENC_Y1_JWH") (class "Default")
      (node (ref "R2") (pin "2") (pinfunction "2_2") (pintype "passive"))
      (node (ref "X_CONN") (pin "2") (pinfunction "2_2") (pintype "passive"))
    )
    (net (code "38") (name "ENC_Y1_WH") (class "Default")
      (node (ref "JP18") (pin "1") (pinfunction "1_1") (pintype "passive"))
      (node (ref "U$2") (pin "P$2") (pinfunction "PB13_P$2") (pintype "bidirectional"))
    )
    (net (code "39") (name "ENC_Y2_GR") (class "Default")
      (node (ref "JP21") (pin "1") (pinfunction "1_1") (pintype "passive"))
      (node (ref "U$2") (pin "P$13") (pinfunction "PB5_P$13") (pintype "bidirectional"))
    )
    (net (code "40") (name "ENC_Y2_JGR") (class "Default")
      (node (ref "R6") (pin "2") (pinfunction "2_2") (pintype "passive"))
      (node (ref "Y2_CONN") (pin "1") (pinfunction "1_1") (pintype "passive"))
    )
    (net (code "41") (name "ENC_Y2_JWH") (class "Default")
      (node (ref "R5") (pin "2") (pinfunction "2_2") (pintype "passive"))
      (node (ref "Y2_CONN") (pin "2") (pinfunction "2_2") (pintype "passive"))
    )
    (net (code "42") (name "ENC_Y2_WH") (class "Default")
      (node (ref "JP20") (pin "1") (pinfunction "1_1") (pintype "passive"))
      (node (ref "U$2") (pin "P$4") (pinfunction "PB15_P$4") (pintype "bidirectional"))
    )
    (net (code "43") (name "ESP32_5V") (class "Default")
      (node (ref "C10") (pin "1") (pinfunction "1_1") (pintype "passive"))
      (node (ref "C3") (pin "1") (pinfunction "+_1") (pintype "passive"))
      (node (ref "ESP_D_CAPS") (pin "1") (pinfunction "1_1") (pintype "passive"))
      (node (ref "IC1") (pin "3") (pinfunction "VO_3") (pintype "passive"))
      (node (ref "J4") (pin "19") (pinfunction "19_19") (pintype "passive"))
      (node (ref "R28") (pin "1") (pinfunction "1_1") (pintype "passive"))
      (node (ref "R29") (pin "1") (pinfunction "1_1") (pintype "passive"))
      (node (ref "R30") (pin "1") (pinfunction "1_1") (pintype "passive"))
      (node (ref "R31") (pin "1") (pinfunction "1_1") (pintype "passive"))
      (node (ref "R32") (pin "1") (pinfunction "1_1") (pintype "passive"))
      (node (ref "R33") (pin "1") (pinfunction "1_1") (pintype "passive"))
      (node (ref "R34") (pin "1") (pinfunction "1_1") (pintype "passive"))
      (node (ref "U$1") (pin "19") (pinfunction "5V_19") (pintype "bidirectional"))
    )
    (net (code "44") (name "ESP32_I2C_JSCL") (class "Default")
      (node (ref "JP14") (pin "2") (pinfunction "2_2") (pintype "passive"))
      (node (ref "U$2") (pin "P$15") (pinfunction "PB7_P$15") (pintype "bidirectional"))
    )
    (net (code "45") (name "ESP32_I2C_JSDA") (class "Default")
      (node (ref "JP15") (pin "2") (pinfunction "2_2") (pintype "passive"))
      (node (ref "U$2") (pin "P$14") (pinfunction "PB6_P$14") (pintype "bidirectional"))
    )
    (net (code "46") (name "ESP32_I2C_SCL") (class "Default")
      (node (ref "J3") (pin "10") (pinfunction "10_10") (pintype "passive"))
      (node (ref "JP14") (pin "1") (pinfunction "1_1") (pintype "passive"))
      (node (ref "U$1") (pin "29") (pinfunction "IO5_29") (pintype "bidirectional"))
    )
    (net (code "47") (name "ESP32_I2C_SDA") (class "Default")
      (node (ref "J3") (pin "11") (pinfunction "11_11") (pintype "passive"))
      (node (ref "JP15") (pin "1") (pinfunction "1_1") (pintype "passive"))
      (node (ref "U$1") (pin "28") (pinfunction "IO17_28") (pintype "bidirectional"))
    )
    (net (code "48") (name "ESP32_JRX") (class "Default")
      (node (ref "ESP_UART") (pin "2") (pinfunction "2_2") (pintype "passive"))
      (node (ref "JP12") (pin "2") (pinfunction "2_2") (pintype "passive"))
    )
    (net (code "49") (name "ESP32_JTX") (class "Default")
      (node (ref "ESP_UART") (pin "1") (pinfunction "1_1") (pintype "passive"))
      (node (ref "JP13") (pin "2") (pinfunction "2_2") (pintype "passive"))
    )
    (net (code "50") (name "ESP32_RX") (class "Default")
      (node (ref "J3") (pin "5") (pinfunction "5_5") (pintype "passive"))
      (node (ref "JP12") (pin "1") (pinfunction "1_1") (pintype "passive"))
      (node (ref "U$1") (pin "34") (pinfunction "RXD0_34") (pintype "bidirectional"))
    )
    (net (code "51") (name "ESP32_TX") (class "Default")
      (node (ref "J3") (pin "4") (pinfunction "4_4") (pintype "passive"))
      (node (ref "JP13") (pin "1") (pinfunction "1_1") (pintype "passive"))
      (node (ref "U$1") (pin "35") (pinfunction "TXD0_35") (pintype "bidirectional"))
    )
    (net (code "52") (name "EXT_P1") (class "Default")
      (node (ref "J3") (pin "15") (pinfunction "15_15") (pintype "passive"))
      (node (ref "JP11") (pin "1") (pinfunction "1_1") (pintype "passive"))
      (node (ref "U$1") (pin "24") (pinfunction "IO2_24") (pintype "bidirectional"))
    )
    (net (code "53") (name "EXT_P2") (class "Default")
      (node (ref "J3") (pin "14") (pinfunction "14_14") (pintype "passive"))
      (node (ref "JP8") (pin "1") (pinfunction "1_1") (pintype "passive"))
      (node (ref "U$1") (pin "25") (pinfunction "IO0_25") (pintype "bidirectional"))
    )
    (net (code "54") (name "EXT_P3") (class "Default")
      (node (ref "J3") (pin "13") (pinfunction "13_13") (pintype "passive"))
      (node (ref "JP9") (pin "1") (pinfunction "1_1") (pintype "passive"))
      (node (ref "U$1") (pin "26") (pinfunction "IO4_26") (pintype "bidirectional"))
    )
    (net (code "55") (name "EXT_P4") (class "Default")
      (node (ref "J3") (pin "12") (pinfunction "12_12") (pintype "passive"))
      (node (ref "JP10") (pin "1") (pinfunction "1_1") (pintype "passive"))
      (node (ref "U$1") (pin "27") (pinfunction "IO16_27") (pintype "bidirectional"))
    )
    (net (code "56") (name "EXT_PJ1") (class "Default")
      (node (ref "EXT_PIN_CONN") (pin "4") (pinfunction "4_4") (pintype "passive"))
      (node (ref "JP11") (pin "2") (pinfunction "2_2") (pintype "passive"))
    )
    (net (code "57") (name "EXT_PJ2") (class "Default")
      (node (ref "EXT_PIN_CONN") (pin "3") (pinfunction "3_3") (pintype "passive"))
      (node (ref "JP8") (pin "2") (pinfunction "2_2") (pintype "passive"))
    )
    (net (code "58") (name "EXT_PJ3") (class "Default")
      (node (ref "EXT_PIN_CONN") (pin "2") (pinfunction "2_2") (pintype "passive"))
      (node (ref "JP9") (pin "2") (pinfunction "2_2") (pintype "passive"))
    )
    (net (code "59") (name "EXT_PJ4") (class "Default")
      (node (ref "EXT_PIN_CONN") (pin "1") (pinfunction "1_1") (pintype "passive"))
      (node (ref "JP10") (pin "2") (pinfunction "2_2") (pintype "passive"))
    )
    (net (code "60") (name "GND") (class "Default")
      (node (ref "12V_LED") (pin "K") (pinfunction "C_K") (pintype "passive"))
      (node (ref "ATMEGA_UART") (pin "3") (pinfunction "3_3") (pintype "passive"))
      (node (ref "AT_LED") (pin "K") (pinfunction "C_K") (pintype "passive"))
      (node (ref "C1") (pin "2") (pinfunction "2_2") (pintype "passive"))
      (node (ref "C10") (pin "2") (pinfunction "2_2") (pintype "passive"))
      (node (ref "C11") (pin "2") (pinfunction "2_2") (pintype "passive"))
      (node (ref "C12") (pin "2") (pinfunction "2_2") (pintype "passive"))
      (node (ref "C13") (pin "1") (pinfunction "1_1") (pintype "passive"))
      (node (ref "C14") (pin "1") (pinfunction "1_1") (pintype "passive"))
      (node (ref "C18") (pin "1") (pinfunction "1_1") (pintype "passive"))
      (node (ref "C19") (pin "1") (pinfunction "1_1") (pintype "passive"))
      (node (ref "C2") (pin "2") (pinfunction "-_2") (pintype "passive"))
      (node (ref "C20") (pin "1") (pinfunction "1_1") (pintype "passive"))
      (node (ref "C21") (pin "1") (pinfunction "1_1") (pintype "passive"))
      (node (ref "C22") (pin "1") (pinfunction "1_1") (pintype "passive"))
      (node (ref "C23") (pin "1") (pinfunction "1_1") (pintype "passive"))
      (node (ref "C24") (pin "1") (pinfunction "1_1") (pintype "passive"))
      (node (ref "C3") (pin "2") (pinfunction "-_2") (pintype "passive"))
      (node (ref "C4") (pin "2") (pinfunction "2_2") (pintype "passive"))
      (node (ref "C5") (pin "2") (pinfunction "-_2") (pintype "passive"))
      (node (ref "C6") (pin "2") (pinfunction "-_2") (pintype "passive"))
      (node (ref "C7") (pin "2") (pinfunction "2_2") (pintype "passive"))
      (node (ref "C8") (pin "2") (pinfunction "-_2") (pintype "passive"))
      (node (ref "C9") (pin "2") (pinfunction "-_2") (pintype "passive"))
      (node (ref "ESP_D_CAPS") (pin "2") (pinfunction "2_2") (pintype "passive"))
      (node (ref "ESP_UART") (pin "3") (pinfunction "3_3") (pintype "passive"))
      (node (ref "IC1") (pin "2") (pinfunction "GND_2") (pintype "passive"))
      (node (ref "IC2") (pin "2") (pinfunction "GND_2") (pintype "passive"))
      (node (ref "IC3") (pin "2") (pinfunction "GND_2") (pintype "passive"))
      (node (ref "ICSP") (pin "6") (pinfunction "GND_6") (pintype "passive"))
      (node (ref "J2") (pin "2") (pinfunction "2_2") (pintype "passive"))
      (node (ref "J3") (pin "1") (pinfunction "1_1") (pintype "passive"))
      (node (ref "J3") (pin "7") (pinfunction "7_7") (pintype "passive"))
      (node (ref "J4") (pin "14") (pinfunction "14_14") (pintype "passive"))
      (node (ref "MOTOR_X") (pin "2") (pinfunction "2_2") (pintype "passive"))
      (node (ref "MOTOR_X") (pin "3") (pinfunction "3_3") (pintype "passive"))
      (node (ref "MOTOR_Y1") (pin "2") (pinfunction "2_2") (pintype "passive"))
      (node (ref "MOTOR_Y1") (pin "3") (pinfunction "3_3") (pintype "passive"))
      (node (ref "MOTOR_Y2") (pin "2") (pinfunction "2_2") (pintype "passive"))
      (node (ref "MOTOR_Y2") (pin "3") (pinfunction "3_3") (pintype "passive"))
      (node (ref "MOTOR_Z") (pin "2") (pinfunction "2_2") (pintype "passive"))
      (node (ref "MOTOR_Z") (pin "3") (pinfunction "3_3") (pintype "passive"))
      (node (ref "OK1") (pin "2") (pinfunction "C_2") (pintype "passive"))
      (node (ref "OK2") (pin "2") (pinfunction "C_2") (pintype "passive"))
      (node (ref "OK3") (pin "2") (pinfunction "C_2") (pintype "passive"))
      (node (ref "OK4") (pin "2") (pinfunction "C_2") (pintype "passive"))
      (node (ref "OK5") (pin "2") (pinfunction "C_2") (pintype "passive"))
      (node (ref "OK6") (pin "2") (pinfunction "C_2") (pintype "passive"))
      (node (ref "OK7") (pin "2") (pinfunction "C_2") (pintype "passive"))
      (node (ref "OK8") (pin "2") (pinfunction "C_2") (pintype "passive"))
      (node (ref "R17") (pin "1") (pinfunction "1_1") (pintype "passive"))
      (node (ref "R18") (pin "1") (pinfunction "1_1") (pintype "passive"))
      (node (ref "R20") (pin "2") (pinfunction "2_2") (pintype "passive"))
      (node (ref "R21") (pin "1") (pinfunction "1_1") (pintype "passive"))
      (node (ref "R22") (pin "1") (pinfunction "1_1") (pintype "passive"))
      (node (ref "R23") (pin "1") (pinfunction "1_1") (pintype "passive"))
      (node (ref "R24") (pin "1") (pinfunction "1_1") (pintype "passive"))
      (node (ref "S1") (pin "3") (pinfunction "3_3") (pintype "passive"))
      (node (ref "STM_D_CAPS1") (pin "2") (pinfunction "2_2") (pintype "passive"))
      (node (ref "STM_UART") (pin "4") (pinfunction "4_4") (pintype "passive"))
      (node (ref "U$1") (pin "14") (pinfunction "GND_14") (pintype "bidirectional"))
      (node (ref "U$1") (pin "32") (pinfunction "GND_32") (pintype "bidirectional"))
      (node (ref "U$1") (pin "38") (pinfunction "GND_38") (pintype "bidirectional"))
      (node (ref "U$2") (pin "P$19") (pinfunction "GND2_P$19") (pintype "bidirectional"))
      (node (ref "U$2") (pin "P$21") (pinfunction "GND1_P$21") (pintype "power_in"))
      (node (ref "U$2") (pin "P$22") (pinfunction "GND_P$22") (pintype "bidirectional"))
      (node (ref "U1") (pin "22") (pinfunction "GND_22") (pintype "bidirectional"))
      (node (ref "U1") (pin "8") (pinfunction "GND_8") (pintype "bidirectional"))
      (node (ref "X_CONN") (pin "4") (pinfunction "4_4") (pintype "passive"))
      (node (ref "Y1_CONN") (pin "4") (pinfunction "4_4") (pintype "passive"))
      (node (ref "Y2_CONN") (pin "4") (pinfunction "4_4") (pintype "passive"))
    )
    (net (code "61") (name "IO13") (class "Default")
      (node (ref "J4") (pin "15") (pinfunction "15_15") (pintype "passive"))
      (node (ref "U$1") (pin "15") (pinfunction "IO13_15") (pintype "bidirectional"))
    )
    (net (code "62") (name "IO15") (class "Default")
      (node (ref "J3") (pin "16") (pinfunction "16_16") (pintype "passive"))
      (node (ref "U$1") (pin "23") (pinfunction "IO15_23") (pintype "bidirectional"))
    )
    (net (code "63") (name "IO18") (class "Default")
      (node (ref "J3") (pin "9") (pinfunction "9_9") (pintype "passive"))
      (node (ref "U$1") (pin "30") (pinfunction "IO18_30") (pintype "bidirectional"))
    )
    (net (code "64") (name "IO19") (class "Default")
      (node (ref "J3") (pin "8") (pinfunction "8_8") (pintype "passive"))
      (node (ref "U$1") (pin "31") (pinfunction "IO19_31") (pintype "bidirectional"))
    )
    (net (code "65") (name "IO21") (class "Default")
      (node (ref "J3") (pin "6") (pinfunction "6_6") (pintype "passive"))
      (node (ref "U$1") (pin "33") (pinfunction "IO21_33") (pintype "bidirectional"))
    )
    (net (code "66") (name "IO34") (class "Default")
      (node (ref "J4") (pin "5") (pinfunction "5_5") (pintype "passive"))
      (node (ref "U$1") (pin "5") (pinfunction "IO34_5") (pintype "bidirectional"))
    )
    (net (code "67") (name "IO35") (class "Default")
      (node (ref "J4") (pin "6") (pinfunction "6_6") (pintype "passive"))
      (node (ref "U$1") (pin "6") (pinfunction "IO35_6") (pintype "bidirectional"))
    )
    (net (code "68") (name "LIMIT_SW1") (class "Default")
      (node (ref "J4") (pin "13") (pinfunction "13_13") (pintype "passive"))
      (node (ref "JP1") (pin "1") (pinfunction "1_1") (pintype "passive"))
      (node (ref "U$1") (pin "13") (pinfunction "IO12_13") (pintype "bidirectional"))
    )
    (net (code "69") (name "LIMIT_SW2") (class "Default")
      (node (ref "J4") (pin "12") (pinfunction "12_12") (pintype "passive"))
      (node (ref "JP2") (pin "1") (pinfunction "1_1") (pintype "passive"))
      (node (ref "U$1") (pin "12") (pinfunction "IO14_12") (pintype "bidirectional"))
    )
    (net (code "70") (name "LIMIT_SW3") (class "Default")
      (node (ref "J4") (pin "11") (pinfunction "11_11") (pintype "passive"))
      (node (ref "JP3") (pin "1") (pinfunction "1_1") (pintype "passive"))
      (node (ref "U$1") (pin "11") (pinfunction "IO27_11") (pintype "bidirectional"))
    )
    (net (code "71") (name "LIMIT_SW4") (class "Default")
      (node (ref "J4") (pin "10") (pinfunction "10_10") (pintype "passive"))
      (node (ref "JP4") (pin "1") (pinfunction "1_1") (pintype "passive"))
      (node (ref "U$1") (pin "10") (pinfunction "IO26_10") (pintype "bidirectional"))
    )
    (net (code "72") (name "LIMIT_SW5") (class "Default")
      (node (ref "J4") (pin "9") (pinfunction "9_9") (pintype "passive"))
      (node (ref "JP5") (pin "1") (pinfunction "1_1") (pintype "passive"))
      (node (ref "U$1") (pin "9") (pinfunction "IO25_9") (pintype "bidirectional"))
    )
    (net (code "73") (name "LIMIT_SW6") (class "Default")
      (node (ref "J4") (pin "8") (pinfunction "8_8") (pintype "passive"))
      (node (ref "JP6") (pin "1") (pinfunction "1_1") (pintype "passive"))
      (node (ref "U$1") (pin "8") (pinfunction "IO33_8") (pintype "bidirectional"))
    )
    (net (code "74") (name "LIMIT_SW7") (class "Default")
      (node (ref "J4") (pin "7") (pinfunction "7_7") (pintype "passive"))
      (node (ref "JP7") (pin "1") (pinfunction "1_1") (pintype "passive"))
      (node (ref "U$1") (pin "7") (pinfunction "IO32_7") (pintype "bidirectional"))
    )
    (net (code "75") (name "LIMIT_SWJ1") (class "Default")
      (node (ref "C22") (pin "2") (pinfunction "2_2") (pintype "passive"))
      (node (ref "JP1") (pin "2") (pinfunction "2_2") (pintype "passive"))
      (node (ref "LIMIT_SW_CONN") (pin "1") (pinfunction "1_1") (pintype "passive"))
      (node (ref "R32") (pin "2") (pinfunction "2_2") (pintype "passive"))
    )
    (net (code "76") (name "LIMIT_SWJ2") (class "Default")
      (node (ref "C20") (pin "2") (pinfunction "2_2") (pintype "passive"))
      (node (ref "JP2") (pin "2") (pinfunction "2_2") (pintype "passive"))
      (node (ref "LIMIT_SW_CONN") (pin "2") (pinfunction "2_2") (pintype "passive"))
      (node (ref "R30") (pin "2") (pinfunction "2_2") (pintype "passive"))
    )
    (net (code "77") (name "LIMIT_SWJ3") (class "Default")
      (node (ref "C18") (pin "2") (pinfunction "2_2") (pintype "passive"))
      (node (ref "JP3") (pin "2") (pinfunction "2_2") (pintype "passive"))
      (node (ref "LIMIT_SW_CONN") (pin "3") (pinfunction "3_3") (pintype "passive"))
      (node (ref "R28") (pin "2") (pinfunction "2_2") (pintype "passive"))
    )
    (net (code "78") (name "LIMIT_SWJ4") (class "Default")
      (node (ref "C19") (pin "2") (pinfunction "2_2") (pintype "passive"))
      (node (ref "JP4") (pin "2") (pinfunction "2_2") (pintype "passive"))
      (node (ref "LIMIT_SW_CONN") (pin "4") (pinfunction "4_4") (pintype "passive"))
      (node (ref "R29") (pin "2") (pinfunction "2_2") (pintype "passive"))
    )
    (net (code "79") (name "LIMIT_SWJ5") (class "Default")
      (node (ref "C21") (pin "2") (pinfunction "2_2") (pintype "passive"))
      (node (ref "JP5") (pin "2") (pinfunction "2_2") (pintype "passive"))
      (node (ref "LIMIT_SW_CONN") (pin "5") (pinfunction "5_5") (pintype "passive"))
      (node (ref "R31") (pin "2") (pinfunction "2_2") (pintype "passive"))
    )
    (net (code "80") (name "LIMIT_SWJ6") (class "Default")
      (node (ref "C23") (pin "2") (pinfunction "2_2") (pintype "passive"))
      (node (ref "JP6") (pin "2") (pinfunction "2_2") (pintype "passive"))
      (node (ref "LIMIT_SW_CONN") (pin "6") (pinfunction "6_6") (pintype "passive"))
      (node (ref "R33") (pin "2") (pinfunction "2_2") (pintype "passive"))
    )
    (net (code "81") (name "LIMIT_SWJ7") (class "Default")
      (node (ref "C24") (pin "2") (pinfunction "2_2") (pintype "passive"))
      (node (ref "JP7") (pin "2") (pinfunction "2_2") (pintype "passive"))
      (node (ref "LIMIT_SW_CONN") (pin "7") (pinfunction "7_7") (pintype "passive"))
      (node (ref "R34") (pin "2") (pinfunction "2_2") (pintype "passive"))
    )
    (net (code "82") (name "Net-(12V_LED-PadA)") (class "Default")
      (node (ref "12V_LED") (pin "A") (pinfunction "A_A") (pintype "passive"))
      (node (ref "500") (pin "2") (pinfunction "2_2") (pintype "passive"))
    )
    (net (code "83") (name "Net-(AT_LED-PadA)") (class "Default")
      (node (ref "AT_LED") (pin "A") (pinfunction "A_A") (pintype "passive"))
      (node (ref "R8") (pin "2") (pinfunction "2_2") (pintype "passive"))
    )
    (net (code "84") (name "Net-(JP16-Pad2)") (class "Default")
      (node (ref "JP16") (pin "2") (pinfunction "2_2") (pintype "passive"))
      (node (ref "R24") (pin "2") (pinfunction "2_2") (pintype "passive"))
      (node (ref "R37") (pin "1") (pinfunction "1_1") (pintype "passive"))
      (node (ref "R4") (pin "1") (pinfunction "1_1") (pintype "passive"))
    )
    (net (code "85") (name "Net-(JP17-Pad2)") (class "Default")
      (node (ref "JP17") (pin "2") (pinfunction "2_2") (pintype "passive"))
      (node (ref "R1") (pin "1") (pinfunction "1_1") (pintype "passive"))
      (node (ref "R17") (pin "2") (pinfunction "2_2") (pintype "passive"))
      (node (ref "R26") (pin "1") (pinfunction "1_1") (pintype "passive"))
    )
    (net (code "86") (name "Net-(JP18-Pad2)") (class "Default")
      (node (ref "JP18") (pin "2") (pinfunction "2_2") (pintype "passive"))
      (node (ref "R18") (pin "2") (pinfunction "2_2") (pintype "passive"))
      (node (ref "R2") (pin "1") (pinfunction "1_1") (pintype "passive"))
      (node (ref "R27") (pin "1") (pinfunction "1_1") (pintype "passive"))
    )
    (net (code "87") (name "Net-(JP19-Pad2)") (class "Default")
      (node (ref "JP19") (pin "2") (pinfunction "2_2") (pintype "passive"))
      (node (ref "R23") (pin "2") (pinfunction "2_2") (pintype "passive"))
      (node (ref "R3") (pin "1") (pinfunction "1_1") (pintype "passive"))
      (node (ref "R38") (pin "1") (pinfunction "1_1") (pintype "passive"))
    )
    (net (code "88") (name "Net-(JP20-Pad2)") (class "Default")
      (node (ref "JP20") (pin "2") (pinfunction "2_2") (pintype "passive"))
      (node (ref "R22") (pin "2") (pinfunction "2_2") (pintype "passive"))
      (node (ref "R36") (pin "1") (pinfunction "1_1") (pintype "passive"))
      (node (ref "R5") (pin "1") (pinfunction "1_1") (pintype "passive"))
    )
    (net (code "89") (name "Net-(JP21-Pad2)") (class "Default")
      (node (ref "JP21") (pin "2") (pinfunction "2_2") (pintype "passive"))
      (node (ref "R21") (pin "2") (pinfunction "2_2") (pintype "passive"))
      (node (ref "R35") (pin "1") (pinfunction "1_1") (pintype "passive"))
      (node (ref "R6") (pin "1") (pinfunction "1_1") (pintype "passive"))
    )
    (net (code "90") (name "Net-(JP23-Pad1)") (class "Default")
      (node (ref "JP23") (pin "1") (pinfunction "1_1") (pintype "passive"))
      (node (ref "R19") (pin "1") (pinfunction "1_1") (pintype "passive"))
    )
    (net (code "91") (name "Net-(OK1-A)") (class "Default")
      (node (ref "OK1") (pin "1") (pinfunction "A_1") (pintype "passive"))
      (node (ref "R11") (pin "2") (pinfunction "2_2") (pintype "passive"))
    )
    (net (code "92") (name "Net-(OK2-A)") (class "Default")
      (node (ref "OK2") (pin "1") (pinfunction "A_1") (pintype "passive"))
      (node (ref "R14") (pin "2") (pinfunction "2_2") (pintype "passive"))
    )
    (net (code "93") (name "Net-(OK3-A)") (class "Default")
      (node (ref "OK3") (pin "1") (pinfunction "A_1") (pintype "passive"))
      (node (ref "R10") (pin "2") (pinfunction "2_2") (pintype "passive"))
    )
    (net (code "94") (name "Net-(OK4-A)") (class "Default")
      (node (ref "OK4") (pin "1") (pinfunction "A_1") (pintype "passive"))
      (node (ref "R9") (pin "2") (pinfunction "2_2") (pintype "passive"))
    )
    (net (code "95") (name "Net-(OK5-A)") (class "Default")
      (node (ref "OK5") (pin "1") (pinfunction "A_1") (pintype "passive"))
      (node (ref "R12") (pin "2") (pinfunction "2_2") (pintype "passive"))
    )
    (net (code "96") (name "Net-(OK6-A)") (class "Default")
      (node (ref "OK6") (pin "1") (pinfunction "A_1") (pintype "passive"))
      (node (ref "R13") (pin "2") (pinfunction "2_2") (pintype "passive"))
    )
    (net (code "97") (name "Net-(OK7-A)") (class "Default")
      (node (ref "OK7") (pin "1") (pinfunction "A_1") (pintype "passive"))
      (node (ref "R15") (pin "2") (pinfunction "2_2") (pintype "passive"))
    )
    (net (code "98") (name "Net-(OK8-A)") (class "Default")
      (node (ref "OK8") (pin "1") (pinfunction "A_1") (pintype "passive"))
      (node (ref "R16") (pin "2") (pinfunction "2_2") (pintype "passive"))
    )
    (net (code "99") (name "Net-(U1-AREF)") (class "Default")
      (node (ref "C7") (pin "1") (pinfunction "1_1") (pintype "passive"))
      (node (ref "U1") (pin "21") (pinfunction "AREF_21") (pintype "bidirectional"))
    )
    (net (code "100") (name "Net-(U1-PB6(XTAL1{slash}TOSC1))") (class "Default")
      (node (ref "C14") (pin "2") (pinfunction "2_2") (pintype "passive"))
      (node (ref "CRYST") (pin "2") (pinfunction "2_2") (pintype "passive"))
      (node (ref "U1") (pin "9") (pinfunction "PB6(XTAL1/TOSC1)_9") (pintype "bidirectional"))
    )
    (net (code "101") (name "Net-(U1-PB7(XTAL2{slash}TOSC2))") (class "Default")
      (node (ref "C13") (pin "2") (pinfunction "2_2") (pintype "passive"))
      (node (ref "CRYST") (pin "1") (pinfunction "1_1") (pintype "passive"))
      (node (ref "U1") (pin "10") (pinfunction "PB7(XTAL2/TOSC2)_10") (pintype "bidirectional"))
    )
    (net (code "102") (name "SD0") (class "Default")
      (node (ref "J3") (pin "18") (pinfunction "18_18") (pintype "passive"))
      (node (ref "U$1") (pin "21") (pinfunction "SD0_21") (pintype "bidirectional"))
    )
    (net (code "103") (name "SD1") (class "Default")
      (node (ref "J3") (pin "17") (pinfunction "17_17") (pintype "passive"))
      (node (ref "U$1") (pin "22") (pinfunction "SD1_22") (pintype "bidirectional"))
    )
    (net (code "104") (name "SD2") (class "Default")
      (node (ref "J4") (pin "16") (pinfunction "16_16") (pintype "passive"))
      (node (ref "U$1") (pin "16") (pinfunction "SD2_16") (pintype "bidirectional"))
    )
    (net (code "105") (name "SD3") (class "Default")
      (node (ref "J4") (pin "17") (pinfunction "17_17") (pintype "passive"))
      (node (ref "U$1") (pin "17") (pinfunction "SD3_17") (pintype "bidirectional"))
    )
    (net (code "106") (name "STEP_X") (class "Default")
      (node (ref "R9") (pin "1") (pinfunction "1_1") (pintype "passive"))
      (node (ref "U1") (pin "4") (pinfunction "PD2(INT0)_4") (pintype "bidirectional"))
    )
    (net (code "107") (name "STEP_XO") (class "Default")
      (node (ref "MOTOR_X") (pin "1") (pinfunction "1_1") (pintype "passive"))
      (node (ref "OK4") (pin "3") (pinfunction "EMIT_3") (pintype "passive"))
    )
    (net (code "108") (name "STEP_Y") (class "Default")
      (node (ref "R10") (pin "1") (pinfunction "1_1") (pintype "passive"))
      (node (ref "R15") (pin "1") (pinfunction "1_1") (pintype "passive"))
      (node (ref "U1") (pin "5") (pinfunction "PD3(INT1)_5") (pintype "bidirectional"))
    )
    (net (code "109") (name "STEP_Y1O") (class "Default")
      (node (ref "MOTOR_Y1") (pin "1") (pinfunction "1_1") (pintype "passive"))
      (node (ref "OK3") (pin "3") (pinfunction "EMIT_3") (pintype "passive"))
    )
    (net (code "110") (name "STEP_Y2O") (class "Default")
      (node (ref "MOTOR_Y2") (pin "1") (pinfunction "1_1") (pintype "passive"))
      (node (ref "OK7") (pin "3") (pinfunction "EMIT_3") (pintype "passive"))
    )
    (net (code "111") (name "STEP_Z") (class "Default")
      (node (ref "R11") (pin "1") (pinfunction "1_1") (pintype "passive"))
      (node (ref "U1") (pin "6") (pinfunction "PD4(XCK/T0)_6") (pintype "bidirectional"))
    )
    (net (code "112") (name "STEP_ZO") (class "Default")
      (node (ref "MOTOR_Z") (pin "1") (pinfunction "1_1") (pintype "passive"))
      (node (ref "OK1") (pin "3") (pinfunction "EMIT_3") (pintype "passive"))
    )
    (net (code "113") (name "STM_5V") (class "Default")
      (node (ref "C11") (pin "1") (pinfunction "1_1") (pintype "passive"))
      (node (ref "C6") (pin "1") (pinfunction "+_1") (pintype "passive"))
      (node (ref "IC2") (pin "3") (pinfunction "VO_3") (pintype "passive"))
      (node (ref "R26") (pin "2") (pinfunction "2_2") (pintype "passive"))
      (node (ref "R27") (pin "2") (pinfunction "2_2") (pintype "passive"))
      (node (ref "R35") (pin "2") (pinfunction "2_2") (pintype "passive"))
      (node (ref "R36") (pin "2") (pinfunction "2_2") (pintype "passive"))
      (node (ref "R37") (pin "2") (pinfunction "2_2") (pintype "passive"))
      (node (ref "R38") (pin "2") (pinfunction "2_2") (pintype "passive"))
      (node (ref "STM_D_CAPS1") (pin "1") (pinfunction "1_1") (pintype "passive"))
      (node (ref "STM_UART") (pin "3") (pinfunction "3_3") (pintype "passive"))
      (node (ref "U$2") (pin "P$18") (pinfunction "5V_P$18") (pintype "bidirectional"))
      (node (ref "X_CONN") (pin "3") (pinfunction "3_3") (pintype "passive"))
      (node (ref "Y1_CONN") (pin "3") (pinfunction "3_3") (pintype "passive"))
      (node (ref "Y2_CONN") (pin "3") (pinfunction "3_3") (pintype "passive"))
    )
    (net (code "114") (name "STM_RX") (class "Default")
      (node (ref "STM_UART") (pin "1") (pinfunction "1_1") (pintype "passive"))
      (node (ref "U$2") (pin "P$6") (pinfunction "PA9_P$6") (pintype "bidirectional"))
    )
    (net (code "115") (name "STM_TX") (class "Default")
      (node (ref "STM_UART") (pin "2") (pinfunction "2_2") (pintype "passive"))
      (node (ref "U$2") (pin "P$7") (pinfunction "PA10_P$7") (pintype "bidirectional"))
    )
    (net (code "116") (name "SVN") (class "Default")
      (node (ref "J4") (pin "4") (pinfunction "4_4") (pintype "passive"))
      (node (ref "U$1") (pin "4") (pinfunction "SVN_4") (pintype "bidirectional"))
    )
    (net (code "117") (name "SVP") (class "Default")
      (node (ref "J4") (pin "3") (pinfunction "3_3") (pintype "passive"))
      (node (ref "U$1") (pin "3") (pinfunction "SVP_3") (pintype "bidirectional"))
    )
    (net (code "118") (name "unconnected-(S1-Pad2)") (class "Default")
      (node (ref "S1") (pin "2") (pinfunction "2_2") (pintype "passive"))
    )
    (net (code "119") (name "unconnected-(S1-Pad4)") (class "Default")
      (node (ref "S1") (pin "4") (pinfunction "4_4") (pintype "passive"))
    )
    (net (code "120") (name "unconnected-(SW3-COM2-Pad5)") (class "Default")
      (node (ref "SW3") (pin "5") (pinfunction "COM2_5") (pintype "passive"))
    )
    (net (code "121") (name "unconnected-(SW3-NC2-Pad4)") (class "Default")
      (node (ref "SW3") (pin "4") (pinfunction "NC2_4") (pintype "passive"))
    )
    (net (code "122") (name "unconnected-(SW3-NO1-Pad3)") (class "Default")
      (node (ref "SW3") (pin "3") (pinfunction "NO1_3") (pintype "passive"))
    )
    (net (code "123") (name "unconnected-(SW3-NO2-Pad6)") (class "Default")
      (node (ref "SW3") (pin "6") (pinfunction "NO2_6") (pintype "passive"))
    )
    (net (code "124") (name "unconnected-(U$2-3.3V-PadP$23)") (class "Default")
      (node (ref "U$2") (pin "P$23") (pinfunction "3.3V_P$23") (pintype "bidirectional"))
    )
    (net (code "125") (name "unconnected-(U$2-3.3V1-PadP$20)") (class "Default")
      (node (ref "U$2") (pin "P$20") (pinfunction "3.3V1_P$20") (pintype "bidirectional"))
    )
    (net (code "126") (name "unconnected-(U$2-PA0-PadP$36)") (class "Default")
      (node (ref "U$2") (pin "P$36") (pinfunction "PA0_P$36") (pintype "bidirectional"))
    )
    (net (code "127") (name "unconnected-(U$2-PA1-PadP$35)") (class "Default")
      (node (ref "U$2") (pin "P$35") (pinfunction "PA1_P$35") (pintype "bidirectional"))
    )
    (net (code "128") (name "unconnected-(U$2-PA2-PadP$34)") (class "Default")
      (node (ref "U$2") (pin "P$34") (pinfunction "PA2_P$34") (pintype "bidirectional"))
    )
    (net (code "129") (name "unconnected-(U$2-PA3-PadP$33)") (class "Default")
      (node (ref "U$2") (pin "P$33") (pinfunction "PA3_P$33") (pintype "bidirectional"))
    )
    (net (code "130") (name "unconnected-(U$2-PA4-PadP$32)") (class "Default")
      (node (ref "U$2") (pin "P$32") (pinfunction "PA4_P$32") (pintype "bidirectional"))
    )
    (net (code "131") (name "unconnected-(U$2-PA5-PadP$31)") (class "Default")
      (node (ref "U$2") (pin "P$31") (pinfunction "PA5_P$31") (pintype "bidirectional"))
    )
    (net (code "132") (name "unconnected-(U$2-PA6-PadP$30)") (class "Default")
      (node (ref "U$2") (pin "P$30") (pinfunction "PA6_P$30") (pintype "bidirectional"))
    )
    (net (code "133") (name "unconnected-(U$2-PA7-PadP$29)") (class "Default")
      (node (ref "U$2") (pin "P$29") (pinfunction "PA7_P$29") (pintype "bidirectional"))
    )
    (net (code "134") (name "unconnected-(U$2-PA8-PadP$5)") (class "Default")
      (node (ref "U$2") (pin "P$5") (pinfunction "PA8_P$5") (pintype "bidirectional"))
    )
    (net (code "135") (name "unconnected-(U$2-PA11-PadP$8)") (class "Default")
      (node (ref "U$2") (pin "P$8") (pinfunction "PA11_P$8") (pintype "bidirectional"))
    )
    (net (code "136") (name "unconnected-(U$2-PA12-PadP$9)") (class "Default")
      (node (ref "U$2") (pin "P$9") (pinfunction "PA12_P$9") (pintype "bidirectional"))
    )
    (net (code "137") (name "unconnected-(U$2-PA15-PadP$10)") (class "Default")
      (node (ref "U$2") (pin "P$10") (pinfunction "PA15_P$10") (pintype "bidirectional"))
    )
    (net (code "138") (name "unconnected-(U$2-PB0-PadP$28)") (class "Default")
      (node (ref "U$2") (pin "P$28") (pinfunction "PB0_P$28") (pintype "bidirectional"))
    )
    (net (code "139") (name "unconnected-(U$2-PB1-PadP$27)") (class "Default")
      (node (ref "U$2") (pin "P$27") (pinfunction "PB1_P$27") (pintype "bidirectional"))
    )
    (net (code "140") (name "unconnected-(U$2-PB3-PadP$11)") (class "Default")
      (node (ref "U$2") (pin "P$11") (pinfunction "PB3_P$11") (pintype "bidirectional"))
    )
    (net (code "141") (name "unconnected-(U$2-PB4-PadP$12)") (class "Default")
      (node (ref "U$2") (pin "P$12") (pinfunction "PB4_P$12") (pintype "bidirectional"))
    )
    (net (code "142") (name "unconnected-(U$2-PB10-PadP$26)") (class "Default")
      (node (ref "U$2") (pin "P$26") (pinfunction "PB10_P$26") (pintype "bidirectional"))
    )
    (net (code "143") (name "unconnected-(U$2-PB11-PadP$25)") (class "Default")
      (node (ref "U$2") (pin "P$25") (pinfunction "PB11_P$25") (pintype "bidirectional"))
    )
    (net (code "144") (name "unconnected-(U$2-PB14-PadP$3)") (class "Default")
      (node (ref "U$2") (pin "P$3") (pinfunction "PB14_P$3") (pintype "bidirectional"))
    )
    (net (code "145") (name "unconnected-(U$2-PC13-PadP$39)") (class "Default")
      (node (ref "U$2") (pin "P$39") (pinfunction "PC13_P$39") (pintype "bidirectional"))
    )
    (net (code "146") (name "unconnected-(U$2-PC14-PadP$38)") (class "Default")
      (node (ref "U$2") (pin "P$38") (pinfunction "PC14_P$38") (pintype "bidirectional"))
    )
    (net (code "147") (name "unconnected-(U$2-PC15-PadP$37)") (class "Default")
      (node (ref "U$2") (pin "P$37") (pinfunction "PC15_P$37") (pintype "bidirectional"))
    )
    (net (code "148") (name "unconnected-(U$2-RESET-PadP$24)") (class "Default")
      (node (ref "U$2") (pin "P$24") (pinfunction "RESET_P$24") (pintype "bidirectional"))
    )
    (net (code "149") (name "unconnected-(U$2-VBAT-PadP$40)") (class "Default")
      (node (ref "U$2") (pin "P$40") (pinfunction "VBAT_P$40") (pintype "bidirectional"))
    )
    (net (code "150") (name "unconnected-(U1-PB0(ICP)-Pad14)") (class "Default")
      (node (ref "U1") (pin "14") (pinfunction "PB0(ICP)_14") (pintype "bidirectional"))
    )
    (net (code "151") (name "unconnected-(U1-PB1(OC1A)-Pad15)") (class "Default")
      (node (ref "U1") (pin "15") (pinfunction "PB1(OC1A)_15") (pintype "bidirectional"))
    )
  )
)
